# lcd_shift_register.net
KiCad netlist of a schematic drawn in EAGLE
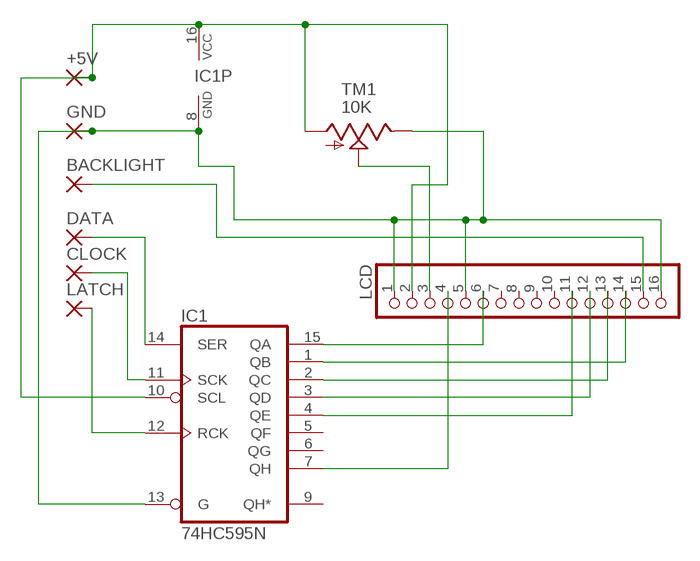
[diagram p0: schematic, sheet 1]

(export (version "E")
  (design (tool "Eeschema 10.0.6"))
  (components
    (comp (ref "+5V")
      (value "2,15/1,0")
      (footprint "eagle-import:2,15_1,0")
      (libsource (lib "eagle-import") (part "2,15/1,0"))
    )
    (comp (ref "BACKLIGHT")
      (value "2,15/1,0")
      (footprint "eagle-import:2,15_1,0")
      (libsource (lib "eagle-import") (part "2,15/1,0"))
    )
    (comp (ref "CLOCK")
      (value "2,15/1,0")
      (footprint "eagle-import:2,15_1,0")
      (libsource (lib "eagle-import") (part "2,15/1,0"))
    )
    (comp (ref "DATA")
      (value "2,15/1,0")
      (footprint "eagle-import:2,15_1,0")
      (libsource (lib "eagle-import") (part "2,15/1,0"))
    )
    (comp (ref "GND")
      (value "2,15/1,0")
      (footprint "eagle-import:2,15_1,0")
      (libsource (lib "eagle-import") (part "2,15/1,0"))
    )
    (comp (ref "IC1")
      (value "74HC595N")
      (footprint "eagle-import:DIL16")
      (libsource (lib "eagle-import") (part "74595NHC"))
    )
    (comp (ref "LATCH")
      (value "2,15/1,0")
      (footprint "eagle-import:2,15_1,0")
      (libsource (lib "eagle-import") (part "2,15/1,0"))
    )
    (comp (ref "LCD")
      (value "PINHD-1X16")
      (footprint "eagle-import:1X16")
      (libsource (lib "eagle-import") (part "PINHD-1X16"))
    )
    (comp (ref "TM1")
      (value "10K")
      (footprint "eagle-import:6MM")
      (libsource (lib "eagle-import") (part "TRIM"))
    )
  )
  (nets
    (net (code "1") (name "Net-(+5V-P)") (class "Default")
      (node (ref "+5V") (pin "1") (pinfunction "P_1") (pintype "passive"))
      (node (ref "IC1") (pin "10") (pinfunction "SCL_10") (pintype "input"))
      (node (ref "IC1") (pin "16") (pinfunction "VCC_16") (pintype "power_in"))
      (node (ref "LCD") (pin "2") (pinfunction "2_2") (pintype "passive"))
      (node (ref "TM1") (pin "A") (pinfunction "A_A") (pintype "passive"))
    )
    (net (code "2") (name "Net-(BACKLIGHT-P)") (class "Default")
      (node (ref "BACKLIGHT") (pin "1") (pinfunction "P_1") (pintype "passive"))
      (node (ref "LCD") (pin "15") (pinfunction "15_15") (pintype "passive"))
    )
    (net (code "3") (name "Net-(CLOCK-P)") (class "Default")
      (node (ref "CLOCK") (pin "1") (pinfunction "P_1") (pintype "passive"))
      (node (ref "IC1") (pin "11") (pinfunction "SCK_11") (pintype "input"))
    )
    (net (code "4") (name "Net-(DATA-P)") (class "Default")
      (node (ref "DATA") (pin "1") (pinfunction "P_1") (pintype "passive"))
      (node (ref "IC1") (pin "14") (pinfunction "SER_14") (pintype "input"))
    )
    (net (code "5") (name "Net-(GND-P)") (class "Default")
      (node (ref "GND") (pin "1") (pinfunction "P_1") (pintype "passive"))
      (node (ref "IC1") (pin "13") (pinfunction "G_13") (pintype "input"))
      (node (ref "IC1") (pin "8") (pinfunction "GND_8") (pintype "power_in"))
      (node (ref "LCD") (pin "1") (pinfunction "1_1") (pintype "passive"))
      (node (ref "LCD") (pin "16") (pinfunction "16_16") (pintype "passive"))
      (node (ref "LCD") (pin "5") (pinfunction "5_5") (pintype "passive"))
      (node (ref "TM1") (pin "E") (pinfunction "E_E") (pintype "passive"))
    )
    (net (code "6") (name "Net-(IC1A-QA)") (class "Default")
      (node (ref "IC1") (pin "15") (pinfunction "QA_15") (pintype "tri_state"))
      (node (ref "LCD") (pin "6") (pinfunction "6_6") (pintype "passive"))
    )
    (net (code "7") (name "Net-(IC1A-QB)") (class "Default")
      (node (ref "IC1") (pin "1") (pinfunction "QB_1") (pintype "tri_state"))
      (node (ref "LCD") (pin "14") (pinfunction "14_14") (pintype "passive"))
    )
    (net (code "8") (name "Net-(IC1A-QC)") (class "Default")
      (node (ref "IC1") (pin "2") (pinfunction "QC_2") (pintype "tri_state"))
      (node (ref "LCD") (pin "13") (pinfunction "13_13") (pintype "passive"))
    )
    (net (code "9") (name "Net-(IC1A-QD)") (class "Default")
      (node (ref "IC1") (pin "3") (pinfunction "QD_3") (pintype "tri_state"))
      (node (ref "LCD") (pin "12") (pinfunction "12_12") (pintype "passive"))
    )
    (net (code "10") (name "Net-(IC1A-QE)") (class "Default")
      (node (ref "IC1") (pin "4") (pinfunction "QE_4") (pintype "tri_state"))
      (node (ref "LCD") (pin "11") (pinfunction "11_11") (pintype "passive"))
    )
    (net (code "11") (name "Net-(IC1A-QH)") (class "Default")
      (node (ref "IC1") (pin "7") (pinfunction "QH_7") (pintype "tri_state"))
      (node (ref "LCD") (pin "4") (pinfunction "4_4") (pintype "passive"))
    )
    (net (code "12") (name "Net-(IC1A-RCK)") (class "Default")
      (node (ref "IC1") (pin "12") (pinfunction "RCK_12") (pintype "input"))
      (node (ref "LATCH") (pin "1") (pinfunction "P_1") (pintype "passive"))
    )
    (net (code "13") (name "Net-(LCD-Pad3)") (class "Default")
      (node (ref "LCD") (pin "3") (pinfunction "3_3") (pintype "passive"))
      (node (ref "TM1") (pin "S") (pinfunction "S_S") (pintype "passive"))
    )
    (net (code "14") (name "unconnected-(IC1A-QF-Pad5)") (class "Default")
      (node (ref "IC1") (pin "5") (pinfunction "QF_5") (pintype "tri_state"))
    )
    (net (code "15") (name "unconnected-(IC1A-QG-Pad6)") (class "Default")
      (node (ref "IC1") (pin "6") (pinfunction "QG_6") (pintype "tri_state"))
    )
    (net (code "16") (name "unconnected-(IC1A-QH*-Pad9)") (class "Default")
      (node (ref "IC1") (pin "9") (pinfunction "QH*_9") (pintype "tri_state"))
    )
    (net (code "17") (name "unconnected-(LCD-Pad7)") (class "Default")
      (node (ref "LCD") (pin "7") (pinfunction "7_7") (pintype "passive"))
    )
    (net (code "18") (name "unconnected-(LCD-Pad8)") (class "Default")
      (node (ref "LCD") (pin "8") (pinfunction "8_8") (pintype "passive"))
    )
    (net (code "19") (name "unconnected-(LCD-Pad9)") (class "Default")
      (node (ref "LCD") (pin "9") (pinfunction "9_9") (pintype "passive"))
    )
    (net (code "20") (name "unconnected-(LCD-Pad10)") (class "Default")
      (node (ref "LCD") (pin "10") (pinfunction "10_10") (pintype "passive"))
    )
  )
)
